# dice.net
KiCad netlist of a schematic drawn in EAGLE
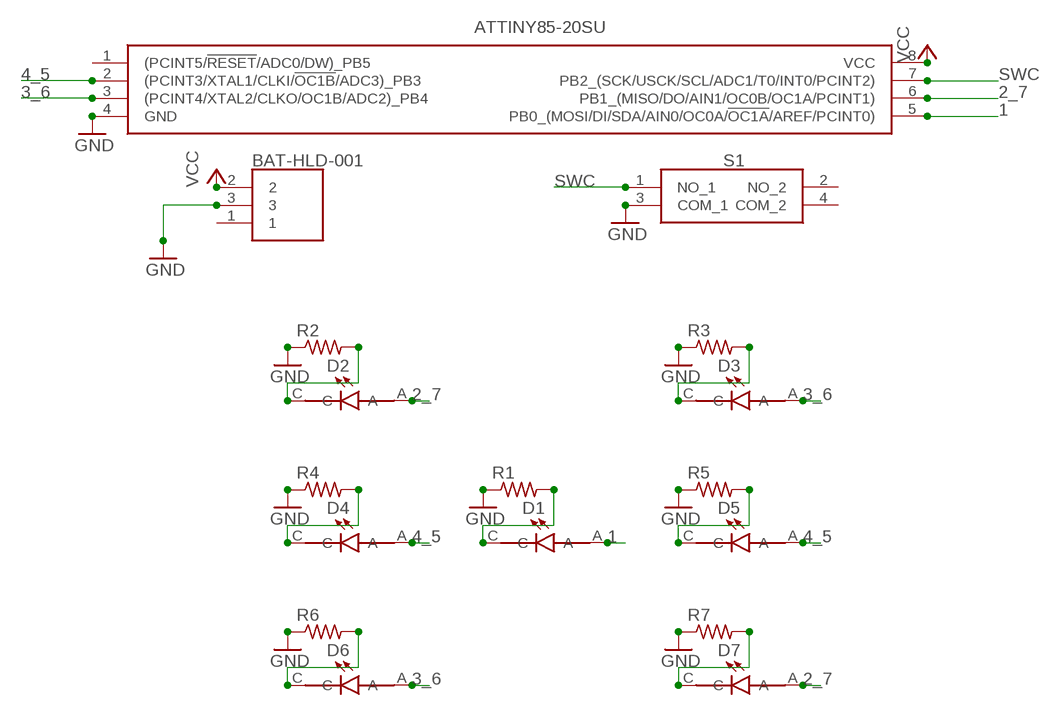
[diagram p0: schematic, sheet 1]

(export (version "E")
  (design (tool "Eeschema 10.0.6"))
  (components
    (comp (ref "D1")
      (value "SML-LXT0805IW-TR")
      (footprint "eagle-import:LEDC2012X120N")
      (fields (field (name "MF") "Lumex Opto/Components"))
      (libsource (lib "eagle-import") (part "SML-LXT0805IW-TR"))
    )
    (comp (ref "D2")
      (value "SML-LXT0805IW-TR")
      (footprint "eagle-import:LEDC2012X120N")
      (fields (field (name "MF") "Lumex Opto/Components"))
      (libsource (lib "eagle-import") (part "SML-LXT0805IW-TR"))
    )
    (comp (ref "D3")
      (value "SML-LXT0805IW-TR")
      (footprint "eagle-import:LEDC2012X120N")
      (fields (field (name "MF") "Lumex Opto/Components"))
      (libsource (lib "eagle-import") (part "SML-LXT0805IW-TR"))
    )
    (comp (ref "D4")
      (value "SML-LXT0805IW-TR")
      (footprint "eagle-import:LEDC2012X120N")
      (fields (field (name "MF") "Lumex Opto/Components"))
      (libsource (lib "eagle-import") (part "SML-LXT0805IW-TR"))
    )
    (comp (ref "D5")
      (value "SML-LXT0805IW-TR")
      (footprint "eagle-import:LEDC2012X120N")
      (fields (field (name "MF") "Lumex Opto/Components"))
      (libsource (lib "eagle-import") (part "SML-LXT0805IW-TR"))
    )
    (comp (ref "D6")
      (value "SML-LXT0805IW-TR")
      (footprint "eagle-import:LEDC2012X120N")
      (fields (field (name "MF") "Lumex Opto/Components"))
      (libsource (lib "eagle-import") (part "SML-LXT0805IW-TR"))
    )
    (comp (ref "D7")
      (value "SML-LXT0805IW-TR")
      (footprint "eagle-import:LEDC2012X120N")
      (fields (field (name "MF") "Lumex Opto/Components"))
      (libsource (lib "eagle-import") (part "SML-LXT0805IW-TR"))
    )
    (comp (ref "IC1")
      (value "ATTINY85-20SU")
      (footprint "eagle-import:SOIC127P798X216-8N")
      (fields (field (name "MOUSER_PART_NUMBER") "556-ATTINY85-20SU"))
      (libsource (lib "eagle-import") (part "ATTINY85-20SU"))
    )
    (comp (ref "R1")
      (value "R-US_R0805")
      (footprint "eagle-import:R0805")
      (libsource (lib "eagle-import") (part "R-US_R0805"))
    )
    (comp (ref "R2")
      (value "R-US_R0805")
      (footprint "eagle-import:R0805")
      (libsource (lib "eagle-import") (part "R-US_R0805"))
    )
    (comp (ref "R3")
      (value "R-US_R0805")
      (footprint "eagle-import:R0805")
      (libsource (lib "eagle-import") (part "R-US_R0805"))
    )
    (comp (ref "R4")
      (value "R-US_R0805")
      (footprint "eagle-import:R0805")
      (libsource (lib "eagle-import") (part "R-US_R0805"))
    )
    (comp (ref "R5")
      (value "R-US_R0805")
      (footprint "eagle-import:R0805")
      (libsource (lib "eagle-import") (part "R-US_R0805"))
    )
    (comp (ref "R6")
      (value "R-US_R0805")
      (footprint "eagle-import:R0805")
      (libsource (lib "eagle-import") (part "R-US_R0805"))
    )
    (comp (ref "R7")
      (value "R-US_R0805")
      (footprint "eagle-import:R0805")
      (libsource (lib "eagle-import") (part "R-US_R0805"))
    )
    (comp (ref "S1")
      (value "TS18-5-20-SL-160-SMT-TR")
      (footprint "eagle-import:TS18520SL160SMTTR")
      (fields (field (name "MOUSER_PART_NUMBER") "179-TS18520SL160SMTT"))
      (libsource (lib "eagle-import") (part "TS18-5-20-SL-160-SMT-TR"))
    )
    (comp (ref "U1")
      (value "BAT-HLD-001")
      (footprint "eagle-import:BATHLD001")
      (fields (field (name "MOUSER_PART_NUMBER") "712-BAT-HLD-001"))
      (libsource (lib "eagle-import") (part "BAT-HLD-001"))
    )
  )
  (nets
    (net (code "1") (name "/1") (class "Default")
      (node (ref "D1") (pin "A") (pinfunction "A_A") (pintype "passive"))
      (node (ref "IC1") (pin "5") (pinfunction "PB0_(MOSI/DI/SDA/AIN0/OC0A/~{OC1A}/AREF/PCINT0)_5") (pintype "bidirectional"))
    )
    (net (code "2") (name "/2_7") (class "Default")
      (node (ref "D2") (pin "A") (pinfunction "A_A") (pintype "passive"))
      (node (ref "D7") (pin "A") (pinfunction "A_A") (pintype "passive"))
      (node (ref "IC1") (pin "6") (pinfunction "PB1_(MISO/DO/AIN1/OC0B/OC1A/PCINT1)_6") (pintype "bidirectional"))
    )
    (net (code "3") (name "/3_6") (class "Default")
      (node (ref "D3") (pin "A") (pinfunction "A_A") (pintype "passive"))
      (node (ref "D6") (pin "A") (pinfunction "A_A") (pintype "passive"))
      (node (ref "IC1") (pin "3") (pinfunction "(PCINT4/XTAL2/CLKO/OC1B/ADC2)_PB4_3") (pintype "bidirectional"))
    )
    (net (code "4") (name "/4_5") (class "Default")
      (node (ref "D4") (pin "A") (pinfunction "A_A") (pintype "passive"))
      (node (ref "D5") (pin "A") (pinfunction "A_A") (pintype "passive"))
      (node (ref "IC1") (pin "2") (pinfunction "(PCINT3/XTAL1/CLKI/~{OC1B}/ADC3)_PB3_2") (pintype "bidirectional"))
    )
    (net (code "5") (name "/SWC") (class "Default")
      (node (ref "IC1") (pin "7") (pinfunction "PB2_(SCK/USCK/SCL/ADC1/T0/INT0/PCINT2)_7") (pintype "bidirectional"))
      (node (ref "S1") (pin "1") (pinfunction "NO_1_1") (pintype "bidirectional"))
    )
    (net (code "6") (name "GND") (class "Default")
      (node (ref "IC1") (pin "4") (pinfunction "GND_4") (pintype "bidirectional"))
      (node (ref "R1") (pin "1") (pinfunction "1_1") (pintype "passive"))
      (node (ref "R2") (pin "1") (pinfunction "1_1") (pintype "passive"))
      (node (ref "R3") (pin "1") (pinfunction "1_1") (pintype "passive"))
      (node (ref "R4") (pin "1") (pinfunction "1_1") (pintype "passive"))
      (node (ref "R5") (pin "1") (pinfunction "1_1") (pintype "passive"))
      (node (ref "R6") (pin "1") (pinfunction "1_1") (pintype "passive"))
      (node (ref "R7") (pin "1") (pinfunction "1_1") (pintype "passive"))
      (node (ref "S1") (pin "3") (pinfunction "COM_1_3") (pintype "bidirectional"))
      (node (ref "U1") (pin "3") (pinfunction "3_3") (pintype "bidirectional"))
    )
    (net (code "7") (name "Net-(D1-PadC)") (class "Default")
      (node (ref "D1") (pin "C") (pinfunction "C_C") (pintype "passive"))
      (node (ref "R1") (pin "2") (pinfunction "2_2") (pintype "passive"))
    )
    (net (code "8") (name "Net-(D2-PadC)") (class "Default")
      (node (ref "D2") (pin "C") (pinfunction "C_C") (pintype "passive"))
      (node (ref "R2") (pin "2") (pinfunction "2_2") (pintype "passive"))
    )
    (net (code "9") (name "Net-(D3-PadC)") (class "Default")
      (node (ref "D3") (pin "C") (pinfunction "C_C") (pintype "passive"))
      (node (ref "R3") (pin "2") (pinfunction "2_2") (pintype "passive"))
    )
    (net (code "10") (name "Net-(D4-PadC)") (class "Default")
      (node (ref "D4") (pin "C") (pinfunction "C_C") (pintype "passive"))
      (node (ref "R4") (pin "2") (pinfunction "2_2") (pintype "passive"))
    )
    (net (code "11") (name "Net-(D5-PadC)") (class "Default")
      (node (ref "D5") (pin "C") (pinfunction "C_C") (pintype "passive"))
      (node (ref "R5") (pin "2") (pinfunction "2_2") (pintype "passive"))
    )
    (net (code "12") (name "Net-(D6-PadC)") (class "Default")
      (node (ref "D6") (pin "C") (pinfunction "C_C") (pintype "passive"))
      (node (ref "R6") (pin "2") (pinfunction "2_2") (pintype "passive"))
    )
    (net (code "13") (name "Net-(D7-PadC)") (class "Default")
      (node (ref "D7") (pin "C") (pinfunction "C_C") (pintype "passive"))
      (node (ref "R7") (pin "2") (pinfunction "2_2") (pintype "passive"))
    )
    (net (code "14") (name "VCC") (class "Default")
      (node (ref "IC1") (pin "8") (pinfunction "VCC_8") (pintype "bidirectional"))
      (node (ref "U1") (pin "2") (pinfunction "2_2") (pintype "bidirectional"))
    )
    (net (code "15") (name "unconnected-(IC1-(PCINT5{slash}~{RESET}{slash}ADC0{slash}DW)_PB5-Pad1)") (class "Default")
      (node (ref "IC1") (pin "1") (pinfunction "(PCINT5/~{RESET}/ADC0/DW)_PB5_1") (pintype "bidirectional"))
    )
    (net (code "16") (name "unconnected-(S1-COM_2-Pad4)") (class "Default")
      (node (ref "S1") (pin "4") (pinfunction "COM_2_4") (pintype "bidirectional"))
    )
    (net (code "17") (name "unconnected-(S1-NO_2-Pad2)") (class "Default")
      (node (ref "S1") (pin "2") (pinfunction "NO_2_2") (pintype "bidirectional"))
    )
    (net (code "18") (name "unconnected-(U1-Pad1)") (class "Default")
      (node (ref "U1") (pin "1") (pinfunction "1_1") (pintype "bidirectional"))
    )
  )
)
